# Converter_3V3-2V5.net
KiCad netlist of a schematic drawn in Altium Designer
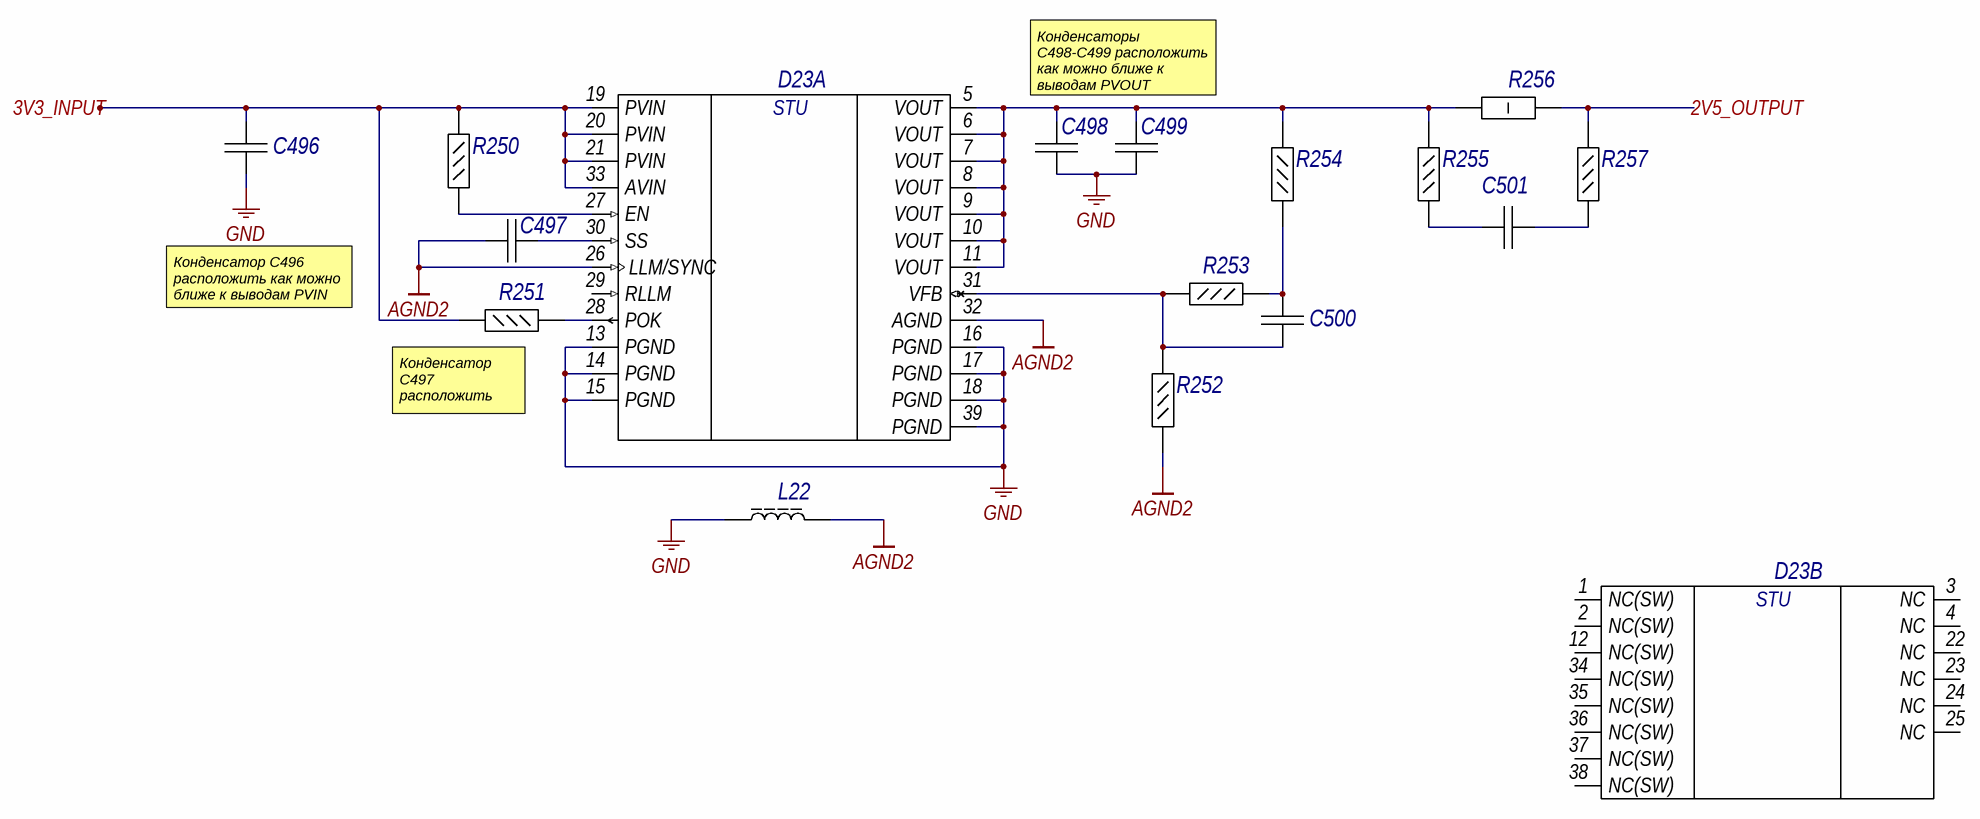
[diagram p0: Converter 3V3-2V5.SchDoc]

(export (version "E")
  (design (tool "Eeschema 10.0.6"))
  (components
    (comp (ref "C496")
      (value "GRM31CR61E226KE15L")
      (footprint "CAPC3216X180X55ML20T25")
      (description "Chip Capacitor, 22 uF, +/- 10%, 25 V, -55 to 85 degC, 1206 (3216 Metric), RoHS, Tape and Reel")
      (fields (field (name "TOLERANCE") "10%"))
      (libsource (lib "MiniPC DB") (part "CAP_NP"))
    )
    (comp (ref "C497")
      (value "VJ0402Y153JXQPW1BC")
      (footprint "CAPC1005X55X23ML05T8")
      (description "Chip Capacitor, 15 nF, +/- 5%, 10 V, -55 to 125 degC, 0402 (1005 Metric), RoHS, Tape and Reel")
      (fields (field (name "TOLERANCE") "5%"))
      (libsource (lib "MiniPC DB") (part "CAP_NP"))
    )
    (comp (ref "C498")
      (value "C3216X5R1A476M160AB")
      (footprint "CAPC3216X180X20ML20")
      (description "Chip Capacitor, 47 uF, +/- 20%, 10 V, -55 to 85 degC, 1206 (3216 Metric), RoHS, Tape and Reel")
      (fields (field (name "TOLERANCE") "20%"))
      (libsource (lib "MiniPC DB") (part "CAP_NP"))
    )
    (comp (ref "C499")
      (value "C3216X5R1A476M160AB")
      (footprint "CAPC3216X180X20ML20")
      (description "Chip Capacitor, 47 uF, +/- 20%, 10 V, -55 to 85 degC, 1206 (3216 Metric), RoHS, Tape and Reel")
      (fields (field (name "TOLERANCE") "20%"))
      (libsource (lib "MiniPC DB") (part "CAP_NP"))
    )
    (comp (ref "C500")
      (value "ECJ-0EC1H150J")
      (footprint "CAPC1005X55X20ML5T10")
      (description "Chip Capacitor,15 pF, +/- 5%, 50 V, -55 to 125 degC, 0402 (1005 Metric), RoHS, Tape and Reel")
      (fields (field (name "TOLERANCE") "5%"))
      (libsource (lib "MiniPC DB") (part "CAP_NP"))
    )
    (comp (ref "C501")
      (value "CGB2A1X5R1E105K033BC")
      (footprint "CAPC1005X33X10LL5")
      (description "Chip Capacitor, 1 uF, +/- 10%, 25 V, -55 to 85 degC, 0402 (1005 Metric), RoHS, Tape and Reel")
      (fields (field (name "TOLERANCE") "10%"))
      (libsource (lib "MiniPC DB") (part "CAP_NP"))
    )
    (comp (ref "D23")
      (value "EN6337QI")
      (footprint "ALTR-QFN-38_A-190_D1-193_V")
      (libsource (lib "MiniPC DB") (part "EN6337QI"))
    )
    (comp (ref "L22")
      (value "742792609")
      (footprint "SMD-0603")
      (description "SMD EMI Suppression Ferrite Bead WE-CBF, Z = 30 Ohm")
      (libsource (lib "MiniPC DB") (part "Choke"))
    )
    (comp (ref "R250")
      (value "ERJ-2GE0R00X")
      (footprint "RESC1005X40X25LL05T05")
      (description "Chip Resistor, 0 mOhm, +/- 5%, 100 mW, -55 to 155 degC, 0402 (1005 Metric), RoHS, Tape and Reel")
      (fields (field (name "TOLERANCE") "5%") (field (name "MANUFACTURER") "Basic Passives"))
      (libsource (lib "") (part "RES-0.05_2"))
    )
    (comp (ref "R251")
      (value "ERJ-2RKF1003X")
      (footprint "RESC1005X40X25LL05T05")
      (description "Chip Resistor, 100 KOhm, +/- 1%, 100 mW, -55 to 155 degC, 0402 (1005 Metric), RoHS, Tape and Reel")
      (fields (field (name "TOLERANCE") "1%") (field (name "MANUFACTURER") "Basic Passives"))
      (libsource (lib "MiniPC DB") (part "RES-0.05"))
    )
    (comp (ref "R252")
      (value "ERJ-2RKF8662X")
      (footprint "RESC1005X40X25LL05T05")
      (description "Chip Resistor, 86.6 KOhm, +/- 1%, 100 mW, -55 to 155 degC, 0402 (1005 Metric), RoHS, Tape and Reel")
      (fields (field (name "TOLERANCE") "1%") (field (name "MANUFACTURER") "Basic Passives"))
      (libsource (lib "") (part "RES-0.05_1"))
    )
    (comp (ref "R253")
      (value "ERJ-2RKF2003X")
      (footprint "RESC1005X40X25LL05T05")
      (description "Chip Resistor, 200 KOhm, +/- 1%, 100 mW, -55 to 155 degC, 0402 (1005 Metric), RoHS, Tape and Reel")
      (fields (field (name "TOLERANCE") "1%") (field (name "MANUFACTURER") "Basic Passives"))
      (libsource (lib "") (part "RES-0.05_1"))
    )
    (comp (ref "R254")
      (value "ERJ-2GE0R00X")
      (footprint "RESC1005X40X25LL05T05")
      (description "Chip Resistor, 0 mOhm, +/- 5%, 100 mW, -55 to 155 degC, 0402 (1005 Metric), RoHS, Tape and Reel")
      (fields (field (name "TOLERANCE") "5%") (field (name "MANUFACTURER") "Basic Passives"))
      (libsource (lib "") (part "RES-0.05_3"))
    )
    (comp (ref "R255")
      (value "ERJ-2RKF1002X")
      (footprint "RESC1005X40X25LL05T05")
      (description "Chip Resistor, 10 KOhm, +/- 1%, 100 mW, -55 to 155 degC, 0402 (1005 Metric), RoHS, Tape and Reel")
      (fields (field (name "TOLERANCE") "1%") (field (name "MANUFACTURER") "Basic Passives"))
      (libsource (lib "") (part "RES-0.05_1"))
    )
    (comp (ref "R256")
      (value "WSLP12061L000FEA")
      (footprint "RESC3216X89X104LL25T25")
      (description "Chip Resistor, 0.001 Ohm, +/- 1%, 1 W, -65 to 170 degC, 1206 (3216 Metric), RoHS, Tape and Reel")
      (fields (field (name "TOLERANCE") "1%"))
      (libsource (lib "MiniPC DB") (part "RES-1"))
    )
    (comp (ref "R257")
      (value "ERJ-2RKF1002X")
      (footprint "RESC1005X40X25LL05T05")
      (description "Chip Resistor, 10 KOhm, +/- 1%, 100 mW, -55 to 155 degC, 0402 (1005 Metric), RoHS, Tape and Reel")
      (fields (field (name "TOLERANCE") "1%") (field (name "MANUFACTURER") "Basic Passives"))
      (libsource (lib "") (part "RES-0.05_1"))
    )
  )
  (nets
    (net (code "1") (name "/2V5_OUTPUT") (class "Default")
      (node (ref "R256") (pin "2") (pinfunction "2_2") (pintype "passive"))
      (node (ref "R257") (pin "2") (pinfunction "2_2") (pintype "passive"))
    )
    (net (code "2") (name "/3V3_INPUT") (class "Default")
      (node (ref "C496") (pin "2") (pinfunction "2_2") (pintype "passive"))
      (node (ref "D23") (pin "19") (pinfunction "PVIN_19") (pintype "power_in"))
      (node (ref "D23") (pin "20") (pinfunction "PVIN_20") (pintype "power_in"))
      (node (ref "D23") (pin "21") (pinfunction "PVIN_21") (pintype "power_in"))
      (node (ref "D23") (pin "33") (pinfunction "AVIN_33") (pintype "power_in"))
      (node (ref "R250") (pin "1") (pinfunction "1_1") (pintype "passive"))
      (node (ref "R251") (pin "1") (pinfunction "1_1") (pintype "passive"))
    )
    (net (code "3") (name "AGND2") (class "Default")
      (node (ref "C497") (pin "1") (pinfunction "1_1") (pintype "passive"))
      (node (ref "D23") (pin "26") (pinfunction "LLM/SYNC_26") (pintype "input"))
      (node (ref "D23") (pin "32") (pinfunction "AGND_32") (pintype "power_in"))
      (node (ref "L22") (pin "2") (pinfunction "2_2") (pintype "passive"))
      (node (ref "R252") (pin "1") (pinfunction "1_1") (pintype "passive"))
    )
    (net (code "4") (name "GND") (class "Default")
      (node (ref "C496") (pin "1") (pinfunction "1_1") (pintype "passive"))
      (node (ref "C498") (pin "1") (pinfunction "1_1") (pintype "passive"))
      (node (ref "C499") (pin "1") (pinfunction "1_1") (pintype "passive"))
      (node (ref "D23") (pin "13") (pinfunction "PGND_13") (pintype "power_in"))
      (node (ref "D23") (pin "14") (pinfunction "PGND_14") (pintype "power_in"))
      (node (ref "D23") (pin "15") (pinfunction "PGND_15") (pintype "power_in"))
      (node (ref "D23") (pin "16") (pinfunction "PGND_16") (pintype "power_in"))
      (node (ref "D23") (pin "17") (pinfunction "PGND_17") (pintype "power_in"))
      (node (ref "D23") (pin "18") (pinfunction "PGND_18") (pintype "power_in"))
      (node (ref "D23") (pin "39") (pinfunction "PGND_39") (pintype "power_in"))
      (node (ref "L22") (pin "1") (pinfunction "1_1") (pintype "passive"))
    )
    (net (code "5") (name "Net-(C498-Pad2)") (class "Default")
      (node (ref "C498") (pin "2") (pinfunction "2_2") (pintype "passive"))
      (node (ref "C499") (pin "2") (pinfunction "2_2") (pintype "passive"))
      (node (ref "D23") (pin "10") (pinfunction "VOUT_10") (pintype "power_in"))
      (node (ref "D23") (pin "11") (pinfunction "VOUT_11") (pintype "power_in"))
      (node (ref "D23") (pin "5") (pinfunction "VOUT_5") (pintype "power_in"))
      (node (ref "D23") (pin "6") (pinfunction "VOUT_6") (pintype "power_in"))
      (node (ref "D23") (pin "7") (pinfunction "VOUT_7") (pintype "power_in"))
      (node (ref "D23") (pin "8") (pinfunction "VOUT_8") (pintype "power_in"))
      (node (ref "D23") (pin "9") (pinfunction "VOUT_9") (pintype "power_in"))
      (node (ref "R254") (pin "1") (pinfunction "1_1") (pintype "passive"))
      (node (ref "R255") (pin "2") (pinfunction "2_2") (pintype "passive"))
      (node (ref "R256") (pin "1") (pinfunction "1_1") (pintype "passive"))
    )
    (net (code "6") (name "Net-(C500-Pad2)") (class "Default")
      (node (ref "C500") (pin "2") (pinfunction "2_2") (pintype "passive"))
      (node (ref "R253") (pin "2") (pinfunction "2_2") (pintype "passive"))
      (node (ref "R254") (pin "2") (pinfunction "2_2") (pintype "passive"))
    )
    (net (code "7") (name "Net-(C501-Pad1)") (class "Default")
      (node (ref "C501") (pin "1") (pinfunction "1_1") (pintype "passive"))
      (node (ref "R255") (pin "1") (pinfunction "1_1") (pintype "passive"))
    )
    (net (code "8") (name "Net-(C501-Pad2)") (class "Default")
      (node (ref "C501") (pin "2") (pinfunction "2_2") (pintype "passive"))
      (node (ref "R257") (pin "1") (pinfunction "1_1") (pintype "passive"))
    )
    (net (code "9") (name "Net-(D23A-EN)") (class "Default")
      (node (ref "D23") (pin "27") (pinfunction "EN_27") (pintype "input"))
      (node (ref "R250") (pin "2") (pinfunction "2_2") (pintype "passive"))
    )
    (net (code "10") (name "Net-(D23A-POK)") (class "Default")
      (node (ref "D23") (pin "28") (pinfunction "POK_28") (pintype "open_collector"))
      (node (ref "R251") (pin "2") (pinfunction "2_2") (pintype "passive"))
    )
    (net (code "11") (name "Net-(D23A-SS)") (class "Default")
      (node (ref "C497") (pin "2") (pinfunction "2_2") (pintype "passive"))
      (node (ref "D23") (pin "30") (pinfunction "SS_30") (pintype "input"))
    )
    (net (code "12") (name "Net-(D23A-VFB)") (class "Default")
      (node (ref "C500") (pin "1") (pinfunction "1_1") (pintype "passive"))
      (node (ref "D23") (pin "31") (pinfunction "VFB_31") (pintype "input"))
      (node (ref "R252") (pin "2") (pinfunction "2_2") (pintype "passive"))
      (node (ref "R253") (pin "1") (pinfunction "1_1") (pintype "passive"))
    )
    (net (code "13") (name "unconnected-(D23A-RLLM-Pad29)") (class "Default")
      (node (ref "D23") (pin "29") (pinfunction "RLLM_29") (pintype "input"))
    )
    (net (code "14") (name "unconnected-(D23B-NC(SW)-Pad1)") (class "Default")
      (node (ref "D23") (pin "1") (pinfunction "NC(SW)_1") (pintype "passive"))
    )
    (net (code "15") (name "unconnected-(D23B-NC(SW)-Pad2)") (class "Default")
      (node (ref "D23") (pin "2") (pinfunction "NC(SW)_2") (pintype "passive"))
    )
    (net (code "16") (name "unconnected-(D23B-NC(SW)-Pad12)") (class "Default")
      (node (ref "D23") (pin "12") (pinfunction "NC(SW)_12") (pintype "passive"))
    )
    (net (code "17") (name "unconnected-(D23B-NC(SW)-Pad34)") (class "Default")
      (node (ref "D23") (pin "34") (pinfunction "NC(SW)_34") (pintype "passive"))
    )
    (net (code "18") (name "unconnected-(D23B-NC(SW)-Pad35)") (class "Default")
      (node (ref "D23") (pin "35") (pinfunction "NC(SW)_35") (pintype "passive"))
    )
    (net (code "19") (name "unconnected-(D23B-NC(SW)-Pad36)") (class "Default")
      (node (ref "D23") (pin "36") (pinfunction "NC(SW)_36") (pintype "passive"))
    )
    (net (code "20") (name "unconnected-(D23B-NC(SW)-Pad37)") (class "Default")
      (node (ref "D23") (pin "37") (pinfunction "NC(SW)_37") (pintype "passive"))
    )
    (net (code "21") (name "unconnected-(D23B-NC(SW)-Pad38)") (class "Default")
      (node (ref "D23") (pin "38") (pinfunction "NC(SW)_38") (pintype "passive"))
    )
    (net (code "22") (name "unconnected-(D23B-NC-Pad3)") (class "Default")
      (node (ref "D23") (pin "3") (pinfunction "NC_3") (pintype "passive"))
    )
    (net (code "23") (name "unconnected-(D23B-NC-Pad4)") (class "Default")
      (node (ref "D23") (pin "4") (pinfunction "NC_4") (pintype "passive"))
    )
    (net (code "24") (name "unconnected-(D23B-NC-Pad22)") (class "Default")
      (node (ref "D23") (pin "22") (pinfunction "NC_22") (pintype "passive"))
    )
    (net (code "25") (name "unconnected-(D23B-NC-Pad23)") (class "Default")
      (node (ref "D23") (pin "23") (pinfunction "NC_23") (pintype "passive"))
    )
    (net (code "26") (name "unconnected-(D23B-NC-Pad24)") (class "Default")
      (node (ref "D23") (pin "24") (pinfunction "NC_24") (pintype "passive"))
    )
    (net (code "27") (name "unconnected-(D23B-NC-Pad25)") (class "Default")
      (node (ref "D23") (pin "25") (pinfunction "NC_25") (pintype "passive"))
    )
  )
)
